# proyecto.net
KiCad netlist of a schematic drawn in EAGLE
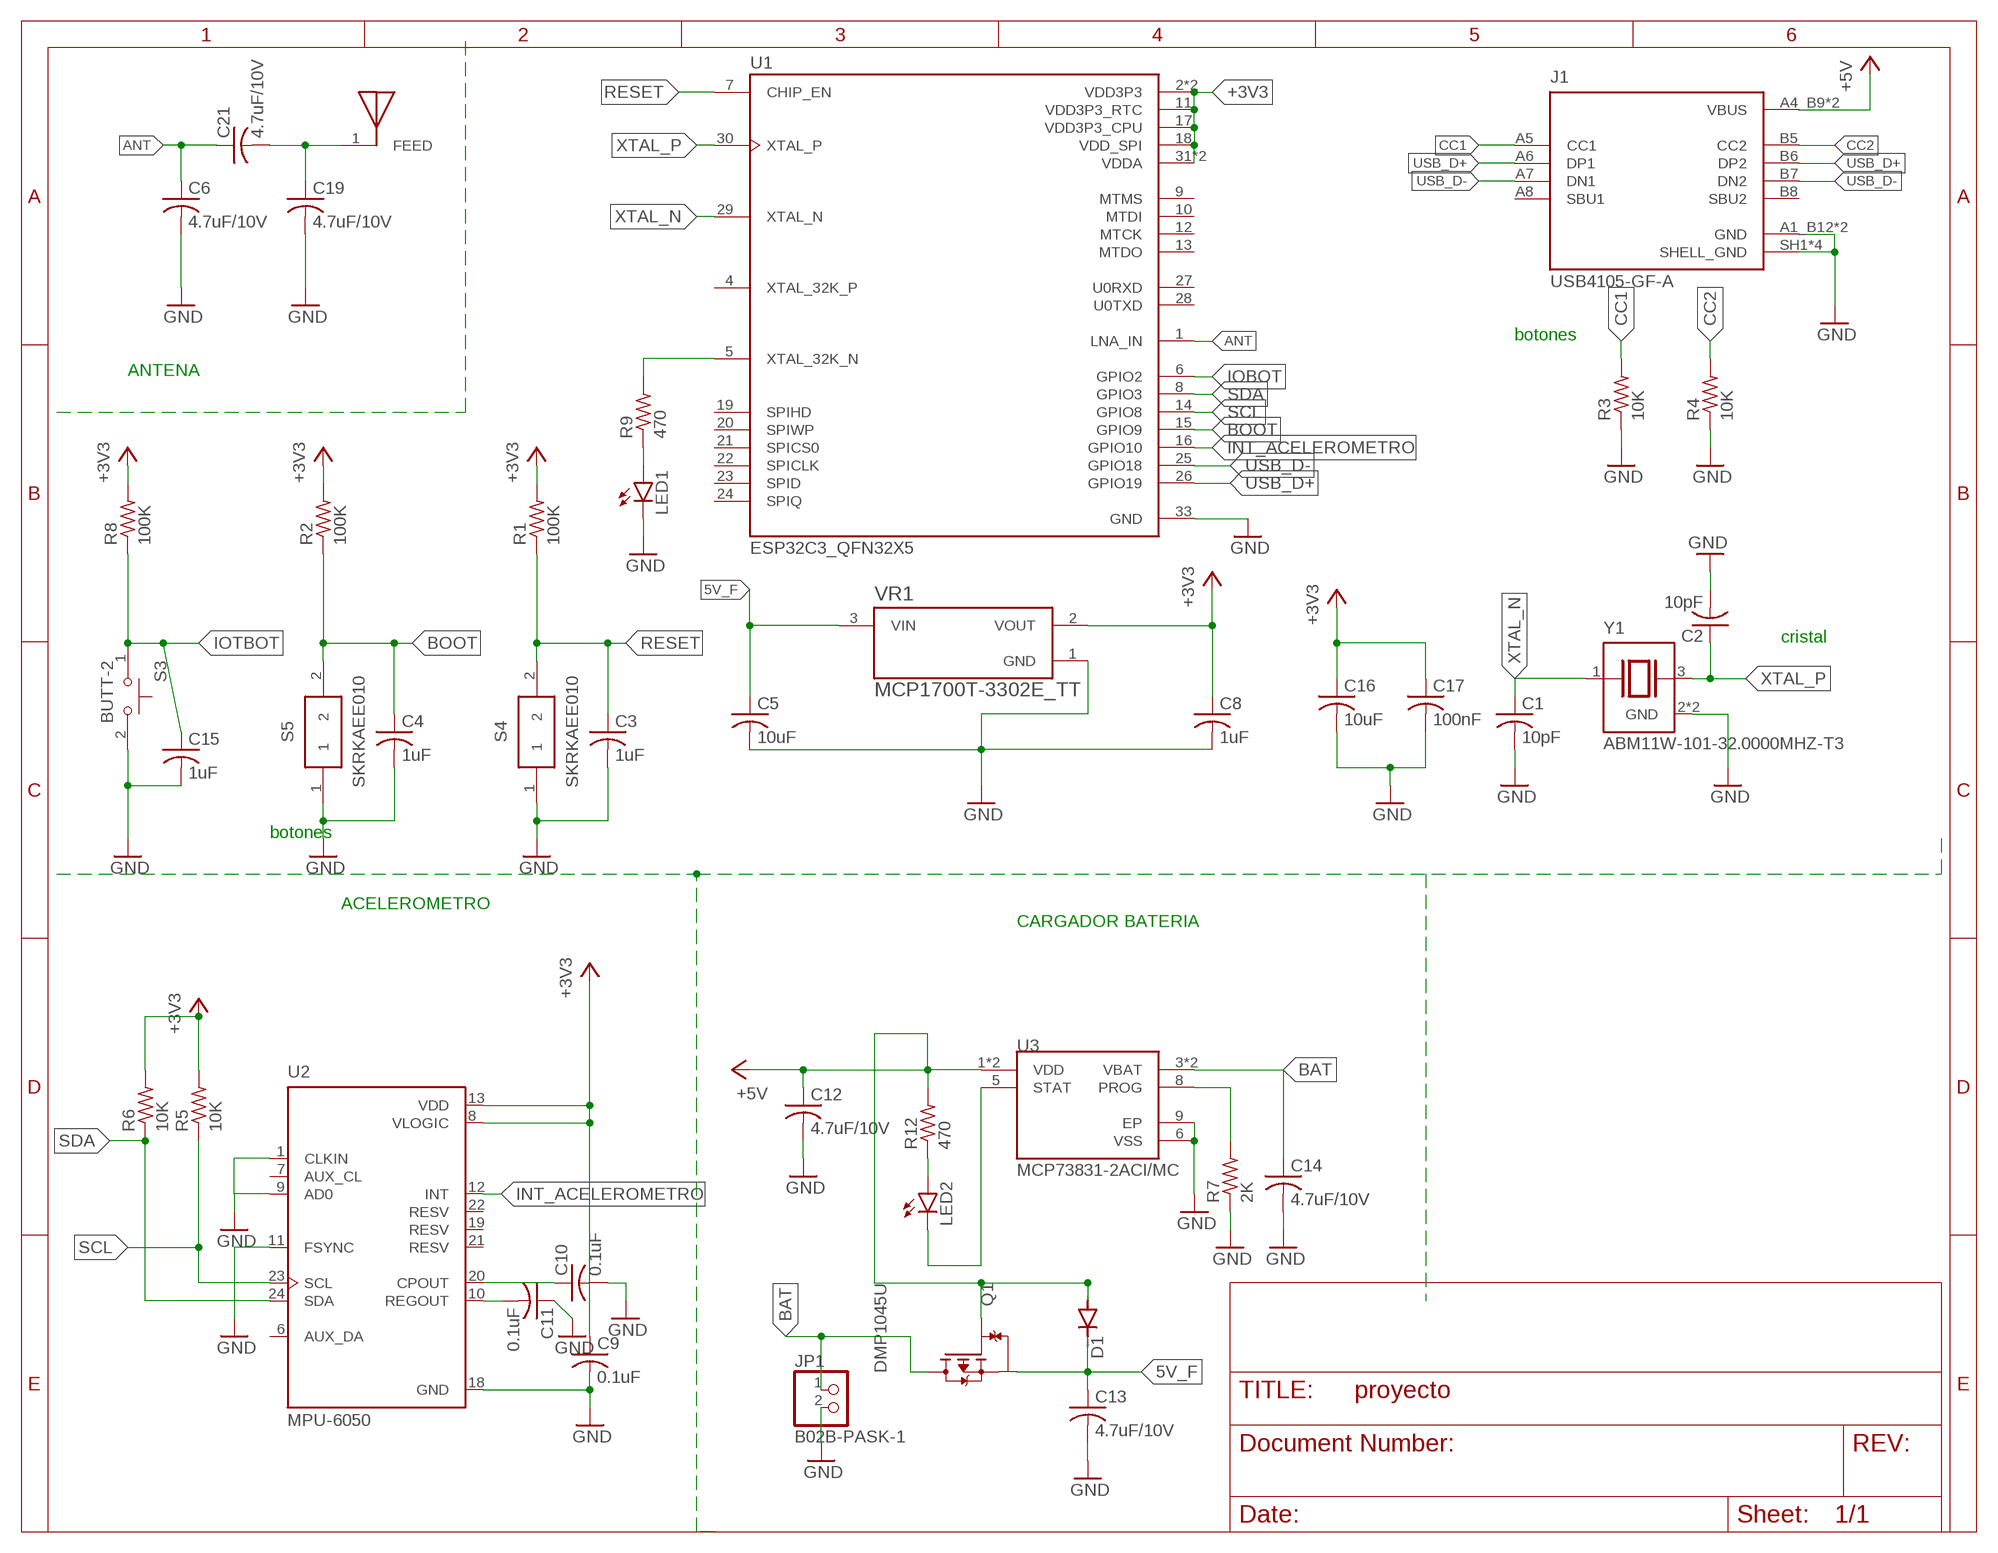
[diagram p0: schematic, sheet 1]

(export (version "E")
  (design (tool "Eeschema 10.0.6"))
  (components
    (comp (ref "C1")
      (value "10pF")
      (footprint "eagle-import:C0603")
      (libsource (lib "eagle-import") (part "C-USC0603"))
    )
    (comp (ref "C2")
      (value "10pF")
      (footprint "eagle-import:C0603")
      (libsource (lib "eagle-import") (part "C-USC0603"))
    )
    (comp (ref "C3")
      (value "1uF")
      (footprint "eagle-import:C0603")
      (libsource (lib "eagle-import") (part "C-USC0603"))
    )
    (comp (ref "C4")
      (value "1uF")
      (footprint "eagle-import:C0603")
      (libsource (lib "eagle-import") (part "C-USC0603"))
    )
    (comp (ref "C5")
      (value "10uF")
      (footprint "eagle-import:C0603")
      (libsource (lib "eagle-import") (part "C-USC0603"))
    )
    (comp (ref "C6")
      (value "4.7uF/10V")
      (footprint "eagle-import:C0603")
      (libsource (lib "eagle-import") (part "C-USC0603"))
    )
    (comp (ref "C8")
      (value "1uF")
      (footprint "eagle-import:C0603")
      (libsource (lib "eagle-import") (part "C-USC0603"))
    )
    (comp (ref "C9")
      (value "0.1uF")
      (footprint "eagle-import:C0603")
      (libsource (lib "eagle-import") (part "C-USC0603"))
    )
    (comp (ref "C10")
      (value "0.1uF")
      (footprint "eagle-import:C0603")
      (libsource (lib "eagle-import") (part "C-USC0603"))
    )
    (comp (ref "C11")
      (value "0.1uF")
      (footprint "eagle-import:C0603")
      (libsource (lib "eagle-import") (part "C-USC0603"))
    )
    (comp (ref "C12")
      (value "4.7uF/10V")
      (footprint "eagle-import:C0603")
      (libsource (lib "eagle-import") (part "C-USC0603"))
    )
    (comp (ref "C13")
      (value "4.7uF/10V")
      (footprint "eagle-import:C0603")
      (libsource (lib "eagle-import") (part "C-USC0603"))
    )
    (comp (ref "C14")
      (value "4.7uF/10V")
      (footprint "eagle-import:C0603")
      (libsource (lib "eagle-import") (part "C-USC0603"))
    )
    (comp (ref "C15")
      (value "1uF")
      (footprint "eagle-import:C0603")
      (libsource (lib "eagle-import") (part "C-USC0603"))
    )
    (comp (ref "C16")
      (value "10uF")
      (footprint "eagle-import:C0603")
      (libsource (lib "eagle-import") (part "C-USC0603"))
    )
    (comp (ref "C17")
      (value "100nF")
      (footprint "eagle-import:C0603")
      (libsource (lib "eagle-import") (part "C-USC0603"))
    )
    (comp (ref "C19")
      (value "4.7uF/10V")
      (footprint "eagle-import:C0603")
      (libsource (lib "eagle-import") (part "C-USC0603"))
    )
    (comp (ref "C21")
      (value "4.7uF/10V")
      (footprint "eagle-import:C0603")
      (libsource (lib "eagle-import") (part "C-USC0603"))
    )
    (comp (ref "D1")
      (value "DIODE-DO214AA")
      (footprint "eagle-import:DO214AA")
      (libsource (lib "eagle-import") (part "DIODE-DO214AA"))
    )
    (comp (ref "J1")
      (value "USB4105-GF-A")
      (footprint "eagle-import:GCT_USB4105-GF-A")
      (fields (field (name "MF") "GCT"))
      (libsource (lib "eagle-import") (part "USB4105-GF-A"))
    )
    (comp (ref "JP1")
      (value "B02B-PASK-1")
      (footprint "eagle-import:B02B-PASK-1")
      (fields (field (name "MF") "JST Sales"))
      (libsource (lib "eagle-import") (part "B02B-PASK-1"))
    )
    (comp (ref "LED1")
      (value "LEDSML0603")
      (footprint "eagle-import:SML0603")
      (libsource (lib "eagle-import") (part "LEDSML0603"))
    )
    (comp (ref "LED2")
      (value "LEDSML0603")
      (footprint "eagle-import:SML0603")
      (libsource (lib "eagle-import") (part "LEDSML0603"))
    )
    (comp (ref "Q1")
      (value "DMP1045U")
      (footprint "eagle-import:SOT91P240X110-3N")
      (fields (field (name "MF") "Diodes Inc."))
      (libsource (lib "eagle-import") (part "DMP1045U"))
    )
    (comp (ref "R1")
      (value "100K")
      (footprint "eagle-import:R0603")
      (libsource (lib "eagle-import") (part "R-US_R0603"))
    )
    (comp (ref "R2")
      (value "100K")
      (footprint "eagle-import:R0603")
      (libsource (lib "eagle-import") (part "R-US_R0603"))
    )
    (comp (ref "R3")
      (value "10K")
      (footprint "eagle-import:R0603")
      (libsource (lib "eagle-import") (part "R-US_R0603"))
    )
    (comp (ref "R4")
      (value "10K")
      (footprint "eagle-import:R0603")
      (libsource (lib "eagle-import") (part "R-US_R0603"))
    )
    (comp (ref "R5")
      (value "10K")
      (footprint "eagle-import:R0603")
      (libsource (lib "eagle-import") (part "R-US_R0603"))
    )
    (comp (ref "R6")
      (value "10K")
      (footprint "eagle-import:R0603")
      (libsource (lib "eagle-import") (part "R-US_R0603"))
    )
    (comp (ref "R7")
      (value "2K")
      (footprint "eagle-import:R0603")
      (libsource (lib "eagle-import") (part "R-US_R0603"))
    )
    (comp (ref "R8")
      (value "100K")
      (footprint "eagle-import:R0603")
      (libsource (lib "eagle-import") (part "R-US_R0603"))
    )
    (comp (ref "R9")
      (value "470")
      (footprint "eagle-import:R0603")
      (libsource (lib "eagle-import") (part "R-US_R0603"))
    )
    (comp (ref "R12")
      (value "470")
      (footprint "eagle-import:R0603")
      (libsource (lib "eagle-import") (part "R-US_R0603"))
    )
    (comp (ref "S3")
      (value "BUTT-2")
      (footprint "eagle-import:SW_BUTT-2")
      (fields (field (name "MF") "Gravitech"))
      (libsource (lib "eagle-import") (part "BUTT-2"))
    )
    (comp (ref "S4")
      (value "SKRKAEE010")
      (footprint "eagle-import:SKRK")
      (fields (field (name "MF") "ALPS"))
      (libsource (lib "eagle-import") (part "SKRKAEE010"))
    )
    (comp (ref "S5")
      (value "SKRKAEE010")
      (footprint "eagle-import:SKRK")
      (fields (field (name "MF") "ALPS"))
      (libsource (lib "eagle-import") (part "SKRKAEE010"))
    )
    (comp (ref "U$1")
      (value "RFANT5220110A0T")
      (footprint "eagle-import:ANTENA")
      (libsource (lib "eagle-import") (part "RFANT5220110A0T"))
    )
    (comp (ref "U1")
      (value "ESP32C3_QFN32X5")
      (footprint "eagle-import:QFN32_5X5MM")
      (fields (field (name "MF") "Espressif Systems") (field (name "MP") "ESP32-C3"))
      (libsource (lib "eagle-import") (part "ESP32C3_QFN32X5"))
    )
    (comp (ref "U2")
      (value "MPU-6050")
      (footprint "eagle-import:QFN50P400X400X95-24N")
      (fields (field (name "MF") "TDK InvenSense"))
      (libsource (lib "eagle-import") (part "MPU-6050"))
    )
    (comp (ref "U3")
      (value "MCP73831-2ACI/MC")
      (footprint "eagle-import:SON50P200X300X100-9N")
      (fields (field (name "MF") "Microchip"))
      (libsource (lib "eagle-import") (part "MCP73831-2ACI/MC"))
    )
    (comp (ref "VR1")
      (value "MCP1700T-3302E_TT")
      (footprint "eagle-import:SOT95P237X112-3N")
      (fields (field (name "MF") "Microchip") (field (name "MP") "MCP1700T-3302E/TT"))
      (libsource (lib "eagle-import") (part "MCP1700T-3302E_TT"))
    )
    (comp (ref "Y1")
      (value "ABM11W-101-32.0000MHZ-T3")
      (footprint "eagle-import:XTAL_ABM11W-101-32.0000MHZ-T3")
      (fields (field (name "MF") "Abracon LLC"))
      (libsource (lib "eagle-import") (part "ABM11W-101-32.0000MHZ-T3"))
    )
  )
  (nets
    (net (code "1") (name "+3V3") (class "Default")
      (node (ref "C16") (pin "1") (pinfunction "1_1") (pintype "passive"))
      (node (ref "C17") (pin "1") (pinfunction "1_1") (pintype "passive"))
      (node (ref "C8") (pin "1") (pinfunction "1_1") (pintype "passive"))
      (node (ref "C9") (pin "1") (pinfunction "1_1") (pintype "passive"))
      (node (ref "R1") (pin "2") (pinfunction "2_2") (pintype "passive"))
      (node (ref "R2") (pin "2") (pinfunction "2_2") (pintype "passive"))
      (node (ref "R5") (pin "2") (pinfunction "2_2") (pintype "passive"))
      (node (ref "R6") (pin "2") (pinfunction "2_2") (pintype "passive"))
      (node (ref "R8") (pin "2") (pinfunction "2_2") (pintype "passive"))
      (node (ref "U1") (pin "11") (pinfunction "VDD3P3_RTC_11") (pintype "power_in"))
      (node (ref "U1") (pin "17") (pinfunction "VDD3P3_CPU_17") (pintype "power_in"))
      (node (ref "U1") (pin "18") (pinfunction "VDD_SPI_18") (pintype "power_in"))
      (node (ref "U1") (pin "2") (pinfunction "VDD3P3_2") (pintype "power_in"))
      (node (ref "U1") (pin "3") (pinfunction "VDD3P3_3") (pintype "power_in"))
      (node (ref "U1") (pin "31") (pinfunction "VDDA_31") (pintype "power_in"))
      (node (ref "U1") (pin "32") (pinfunction "VDDA_32") (pintype "power_in"))
      (node (ref "U2") (pin "13") (pinfunction "VDD_13") (pintype "power_in"))
      (node (ref "U2") (pin "8") (pinfunction "VLOGIC_8") (pintype "power_in"))
      (node (ref "VR1") (pin "2") (pinfunction "VOUT_2") (pintype "output"))
    )
    (net (code "2") (name "+5V") (class "Default")
      (node (ref "C12") (pin "1") (pinfunction "1_1") (pintype "passive"))
      (node (ref "D1") (pin "A") (pinfunction "A_A") (pintype "passive"))
      (node (ref "J1") (pin "A4_B9") (pinfunction "VBUS_A4_B9") (pintype "power_in"))
      (node (ref "J1") (pin "B4_A9") (pinfunction "VBUS_B4_A9") (pintype "power_in"))
      (node (ref "Q1") (pin "1") (pinfunction "G_1") (pintype "passive"))
      (node (ref "R12") (pin "2") (pinfunction "2_2") (pintype "passive"))
      (node (ref "U3") (pin "1") (pinfunction "VDD_1") (pintype "power_in"))
      (node (ref "U3") (pin "2") (pinfunction "VDD_2") (pintype "power_in"))
    )
    (net (code "3") (name "5V_F") (class "Default")
      (node (ref "C13") (pin "1") (pinfunction "1_1") (pintype "passive"))
      (node (ref "C5") (pin "1") (pinfunction "1_1") (pintype "passive"))
      (node (ref "D1") (pin "C") (pinfunction "C_C") (pintype "passive"))
      (node (ref "Q1") (pin "2") (pinfunction "S_2") (pintype "passive"))
      (node (ref "VR1") (pin "3") (pinfunction "VIN_3") (pintype "input"))
    )
    (net (code "4") (name "ANT") (class "Default")
      (node (ref "C21") (pin "1") (pinfunction "1_1") (pintype "passive"))
      (node (ref "C6") (pin "1") (pinfunction "1_1") (pintype "passive"))
      (node (ref "U1") (pin "1") (pinfunction "LNA_IN_1") (pintype "bidirectional"))
    )
    (net (code "5") (name "BAT") (class "Default")
      (node (ref "C14") (pin "1") (pinfunction "1_1") (pintype "passive"))
      (node (ref "JP1") (pin "1") (pinfunction "1_1") (pintype "passive"))
      (node (ref "Q1") (pin "3") (pinfunction "D_3") (pintype "passive"))
      (node (ref "U3") (pin "3") (pinfunction "VBAT_3") (pintype "output"))
      (node (ref "U3") (pin "4") (pinfunction "VBAT_4") (pintype "output"))
    )
    (net (code "6") (name "BOOT") (class "Default")
      (node (ref "C4") (pin "1") (pinfunction "1_1") (pintype "passive"))
      (node (ref "R2") (pin "1") (pinfunction "1_1") (pintype "passive"))
      (node (ref "S5") (pin "2") (pinfunction "2_2") (pintype "passive"))
      (node (ref "U1") (pin "15") (pinfunction "GPIO9_15") (pintype "bidirectional"))
    )
    (net (code "7") (name "CC1") (class "Default")
      (node (ref "J1") (pin "A5") (pinfunction "CC1_A5") (pintype "bidirectional"))
      (node (ref "R3") (pin "2") (pinfunction "2_2") (pintype "passive"))
    )
    (net (code "8") (name "CC2") (class "Default")
      (node (ref "J1") (pin "B5") (pinfunction "CC2_B5") (pintype "bidirectional"))
      (node (ref "R4") (pin "2") (pinfunction "2_2") (pintype "passive"))
    )
    (net (code "9") (name "GND") (class "Default")
      (node (ref "C1") (pin "2") (pinfunction "2_2") (pintype "passive"))
      (node (ref "C10") (pin "2") (pinfunction "2_2") (pintype "passive"))
      (node (ref "C11") (pin "1") (pinfunction "1_1") (pintype "passive"))
      (node (ref "C12") (pin "2") (pinfunction "2_2") (pintype "passive"))
      (node (ref "C13") (pin "2") (pinfunction "2_2") (pintype "passive"))
      (node (ref "C14") (pin "2") (pinfunction "2_2") (pintype "passive"))
      (node (ref "C15") (pin "2") (pinfunction "2_2") (pintype "passive"))
      (node (ref "C16") (pin "2") (pinfunction "2_2") (pintype "passive"))
      (node (ref "C17") (pin "2") (pinfunction "2_2") (pintype "passive"))
      (node (ref "C19") (pin "2") (pinfunction "2_2") (pintype "passive"))
      (node (ref "C2") (pin "2") (pinfunction "2_2") (pintype "passive"))
      (node (ref "C3") (pin "2") (pinfunction "2_2") (pintype "passive"))
      (node (ref "C4") (pin "2") (pinfunction "2_2") (pintype "passive"))
      (node (ref "C5") (pin "2") (pinfunction "2_2") (pintype "passive"))
      (node (ref "C6") (pin "2") (pinfunction "2_2") (pintype "passive"))
      (node (ref "C8") (pin "2") (pinfunction "2_2") (pintype "passive"))
      (node (ref "C9") (pin "2") (pinfunction "2_2") (pintype "passive"))
      (node (ref "J1") (pin "A1_B12") (pinfunction "GND_A1_B12") (pintype "power_in"))
      (node (ref "J1") (pin "B1_A12") (pinfunction "GND_B1_A12") (pintype "power_in"))
      (node (ref "J1") (pin "SH1") (pinfunction "SHELL_GND_SH1") (pintype "power_in"))
      (node (ref "J1") (pin "SH2") (pinfunction "SHELL_GND_SH2") (pintype "power_in"))
      (node (ref "J1") (pin "SH3") (pinfunction "SHELL_GND_SH3") (pintype "power_in"))
      (node (ref "J1") (pin "SH4") (pinfunction "SHELL_GND_SH4") (pintype "power_in"))
      (node (ref "JP1") (pin "2") (pinfunction "2_2") (pintype "passive"))
      (node (ref "LED1") (pin "C") (pinfunction "C_C") (pintype "passive"))
      (node (ref "R3") (pin "1") (pinfunction "1_1") (pintype "passive"))
      (node (ref "R4") (pin "1") (pinfunction "1_1") (pintype "passive"))
      (node (ref "R7") (pin "1") (pinfunction "1_1") (pintype "passive"))
      (node (ref "S3") (pin "2") (pinfunction "2_2") (pintype "passive"))
      (node (ref "S4") (pin "1") (pinfunction "1_1") (pintype "passive"))
      (node (ref "S5") (pin "1") (pinfunction "1_1") (pintype "passive"))
      (node (ref "U1") (pin "33") (pinfunction "GND_33") (pintype "power_in"))
      (node (ref "U2") (pin "1") (pinfunction "CLKIN_1") (pintype "input"))
      (node (ref "U2") (pin "11") (pinfunction "FSYNC_11") (pintype "input"))
      (node (ref "U2") (pin "18") (pinfunction "GND_18") (pintype "power_in"))
      (node (ref "U2") (pin "9") (pinfunction "AD0_9") (pintype "input"))
      (node (ref "U3") (pin "6") (pinfunction "VSS_6") (pintype "power_in"))
      (node (ref "U3") (pin "9") (pinfunction "EP_9") (pintype "power_in"))
      (node (ref "VR1") (pin "1") (pinfunction "GND_1") (pintype "power_in"))
      (node (ref "Y1") (pin "2") (pinfunction "GND_2") (pintype "power_in"))
      (node (ref "Y1") (pin "4") (pinfunction "GND_4") (pintype "power_in"))
    )
    (net (code "10") (name "INT_ACELEROMETRO") (class "Default")
      (node (ref "U1") (pin "16") (pinfunction "GPIO10_16") (pintype "bidirectional"))
      (node (ref "U2") (pin "12") (pinfunction "INT_12") (pintype "output"))
    )
    (net (code "11") (name "IOBOT") (class "Default")
      (node (ref "U1") (pin "6") (pinfunction "GPIO2_6") (pintype "bidirectional"))
    )
    (net (code "12") (name "IOTBOT") (class "Default")
      (node (ref "C15") (pin "1") (pinfunction "1_1") (pintype "passive"))
      (node (ref "R8") (pin "1") (pinfunction "1_1") (pintype "passive"))
      (node (ref "S3") (pin "1") (pinfunction "1_1") (pintype "passive"))
    )
    (net (code "13") (name "Net-(LED1-PadA)") (class "Default")
      (node (ref "LED1") (pin "A") (pinfunction "A_A") (pintype "passive"))
      (node (ref "R9") (pin "1") (pinfunction "1_1") (pintype "passive"))
    )
    (net (code "14") (name "Net-(LED2-PadA)") (class "Default")
      (node (ref "LED2") (pin "A") (pinfunction "A_A") (pintype "passive"))
      (node (ref "R12") (pin "1") (pinfunction "1_1") (pintype "passive"))
    )
    (net (code "15") (name "Net-(U$1-FEED)") (class "Default")
      (node (ref "C19") (pin "1") (pinfunction "1_1") (pintype "passive"))
      (node (ref "C21") (pin "2") (pinfunction "2_2") (pintype "passive"))
      (node (ref "U$1") (pin "1") (pinfunction "FEED_1") (pintype "bidirectional"))
    )
    (net (code "16") (name "Net-(U1-XTAL_32K_N)") (class "Default")
      (node (ref "R9") (pin "2") (pinfunction "2_2") (pintype "passive"))
      (node (ref "U1") (pin "5") (pinfunction "XTAL_32K_N_5") (pintype "bidirectional"))
    )
    (net (code "17") (name "Net-(U2-CPOUT)") (class "Default")
      (node (ref "C10") (pin "1") (pinfunction "1_1") (pintype "passive"))
      (node (ref "U2") (pin "20") (pinfunction "CPOUT_20") (pintype "passive"))
    )
    (net (code "18") (name "Net-(U2-REGOUT)") (class "Default")
      (node (ref "C11") (pin "2") (pinfunction "2_2") (pintype "passive"))
      (node (ref "U2") (pin "10") (pinfunction "REGOUT_10") (pintype "passive"))
    )
    (net (code "19") (name "Net-(U3-PROG)") (class "Default")
      (node (ref "R7") (pin "2") (pinfunction "2_2") (pintype "passive"))
      (node (ref "U3") (pin "8") (pinfunction "PROG_8") (pintype "input"))
    )
    (net (code "20") (name "Net-(U3-STAT)") (class "Default")
      (node (ref "LED2") (pin "C") (pinfunction "C_C") (pintype "passive"))
      (node (ref "U3") (pin "5") (pinfunction "STAT_5") (pintype "output"))
    )
    (net (code "21") (name "RESET") (class "Default")
      (node (ref "C3") (pin "1") (pinfunction "1_1") (pintype "passive"))
      (node (ref "R1") (pin "1") (pinfunction "1_1") (pintype "passive"))
      (node (ref "S4") (pin "2") (pinfunction "2_2") (pintype "passive"))
      (node (ref "U1") (pin "7") (pinfunction "CHIP_EN_7") (pintype "input"))
    )
    (net (code "22") (name "SCL") (class "Default")
      (node (ref "R5") (pin "1") (pinfunction "1_1") (pintype "passive"))
      (node (ref "U1") (pin "14") (pinfunction "GPIO8_14") (pintype "bidirectional"))
      (node (ref "U2") (pin "23") (pinfunction "SCL_23") (pintype "input"))
    )
    (net (code "23") (name "SDA") (class "Default")
      (node (ref "R6") (pin "1") (pinfunction "1_1") (pintype "passive"))
      (node (ref "U1") (pin "8") (pinfunction "GPIO3_8") (pintype "bidirectional"))
      (node (ref "U2") (pin "24") (pinfunction "SDA_24") (pintype "bidirectional"))
    )
    (net (code "24") (name "USB_D+") (class "Default")
      (node (ref "J1") (pin "A6") (pinfunction "DP1_A6") (pintype "bidirectional"))
      (node (ref "J1") (pin "B6") (pinfunction "DP2_B6") (pintype "bidirectional"))
      (node (ref "U1") (pin "26") (pinfunction "GPIO19_26") (pintype "bidirectional"))
    )
    (net (code "25") (name "USB_D-") (class "Default")
      (node (ref "J1") (pin "A7") (pinfunction "DN1_A7") (pintype "bidirectional"))
      (node (ref "J1") (pin "B7") (pinfunction "DN2_B7") (pintype "bidirectional"))
      (node (ref "U1") (pin "25") (pinfunction "GPIO18_25") (pintype "bidirectional"))
    )
    (net (code "26") (name "XTAL_N") (class "Default")
      (node (ref "C1") (pin "1") (pinfunction "1_1") (pintype "passive"))
      (node (ref "U1") (pin "29") (pinfunction "XTAL_N_29") (pintype "output"))
      (node (ref "Y1") (pin "1") (pinfunction "1_1") (pintype "passive"))
    )
    (net (code "27") (name "XTAL_P") (class "Default")
      (node (ref "C2") (pin "1") (pinfunction "1_1") (pintype "passive"))
      (node (ref "U1") (pin "30") (pinfunction "XTAL_P_30") (pintype "input"))
      (node (ref "Y1") (pin "3") (pinfunction "2_3") (pintype "passive"))
    )
    (net (code "28") (name "unconnected-(J1-SBU1-PadA8)") (class "Default")
      (node (ref "J1") (pin "A8") (pinfunction "SBU1_A8") (pintype "bidirectional"))
    )
    (net (code "29") (name "unconnected-(J1-SBU2-PadB8)") (class "Default")
      (node (ref "J1") (pin "B8") (pinfunction "SBU2_B8") (pintype "bidirectional"))
    )
    (net (code "30") (name "unconnected-(U1-MTCK-Pad12)") (class "Default")
      (node (ref "U1") (pin "12") (pinfunction "MTCK_12") (pintype "bidirectional"))
    )
    (net (code "31") (name "unconnected-(U1-MTDI-Pad10)") (class "Default")
      (node (ref "U1") (pin "10") (pinfunction "MTDI_10") (pintype "bidirectional"))
    )
    (net (code "32") (name "unconnected-(U1-MTDO-Pad13)") (class "Default")
      (node (ref "U1") (pin "13") (pinfunction "MTDO_13") (pintype "bidirectional"))
    )
    (net (code "33") (name "unconnected-(U1-MTMS-Pad9)") (class "Default")
      (node (ref "U1") (pin "9") (pinfunction "MTMS_9") (pintype "bidirectional"))
    )
    (net (code "34") (name "unconnected-(U1-SPICLK-Pad22)") (class "Default")
      (node (ref "U1") (pin "22") (pinfunction "SPICLK_22") (pintype "bidirectional"))
    )
    (net (code "35") (name "unconnected-(U1-SPICS0-Pad21)") (class "Default")
      (node (ref "U1") (pin "21") (pinfunction "SPICS0_21") (pintype "bidirectional"))
    )
    (net (code "36") (name "unconnected-(U1-SPID-Pad23)") (class "Default")
      (node (ref "U1") (pin "23") (pinfunction "SPID_23") (pintype "bidirectional"))
    )
    (net (code "37") (name "unconnected-(U1-SPIHD-Pad19)") (class "Default")
      (node (ref "U1") (pin "19") (pinfunction "SPIHD_19") (pintype "bidirectional"))
    )
    (net (code "38") (name "unconnected-(U1-SPIQ-Pad24)") (class "Default")
      (node (ref "U1") (pin "24") (pinfunction "SPIQ_24") (pintype "bidirectional"))
    )
    (net (code "39") (name "unconnected-(U1-SPIWP-Pad20)") (class "Default")
      (node (ref "U1") (pin "20") (pinfunction "SPIWP_20") (pintype "bidirectional"))
    )
    (net (code "40") (name "unconnected-(U1-U0RXD-Pad27)") (class "Default")
      (node (ref "U1") (pin "27") (pinfunction "U0RXD_27") (pintype "bidirectional"))
    )
    (net (code "41") (name "unconnected-(U1-U0TXD-Pad28)") (class "Default")
      (node (ref "U1") (pin "28") (pinfunction "U0TXD_28") (pintype "bidirectional"))
    )
    (net (code "42") (name "unconnected-(U1-XTAL_32K_P-Pad4)") (class "Default")
      (node (ref "U1") (pin "4") (pinfunction "XTAL_32K_P_4") (pintype "bidirectional"))
    )
    (net (code "43") (name "unconnected-(U2-AUX_CL-Pad7)") (class "Default")
      (node (ref "U2") (pin "7") (pinfunction "AUX_CL_7") (pintype "input"))
    )
    (net (code "44") (name "unconnected-(U2-AUX_DA-Pad6)") (class "Default")
      (node (ref "U2") (pin "6") (pinfunction "AUX_DA_6") (pintype "bidirectional"))
    )
    (net (code "45") (name "unconnected-(U2-RESV-Pad19)") (class "Default")
      (node (ref "U2") (pin "19") (pinfunction "RESV_19") (pintype "passive"))
    )
    (net (code "46") (name "unconnected-(U2-RESV-Pad21)") (class "Default")
      (node (ref "U2") (pin "21") (pinfunction "RESV_21") (pintype "passive"))
    )
    (net (code "47") (name "unconnected-(U2-RESV-Pad22)") (class "Default")
      (node (ref "U2") (pin "22") (pinfunction "RESV_22") (pintype "passive"))
    )
  )
)
